# Power.net
KiCad netlist of a schematic drawn in Altium Designer
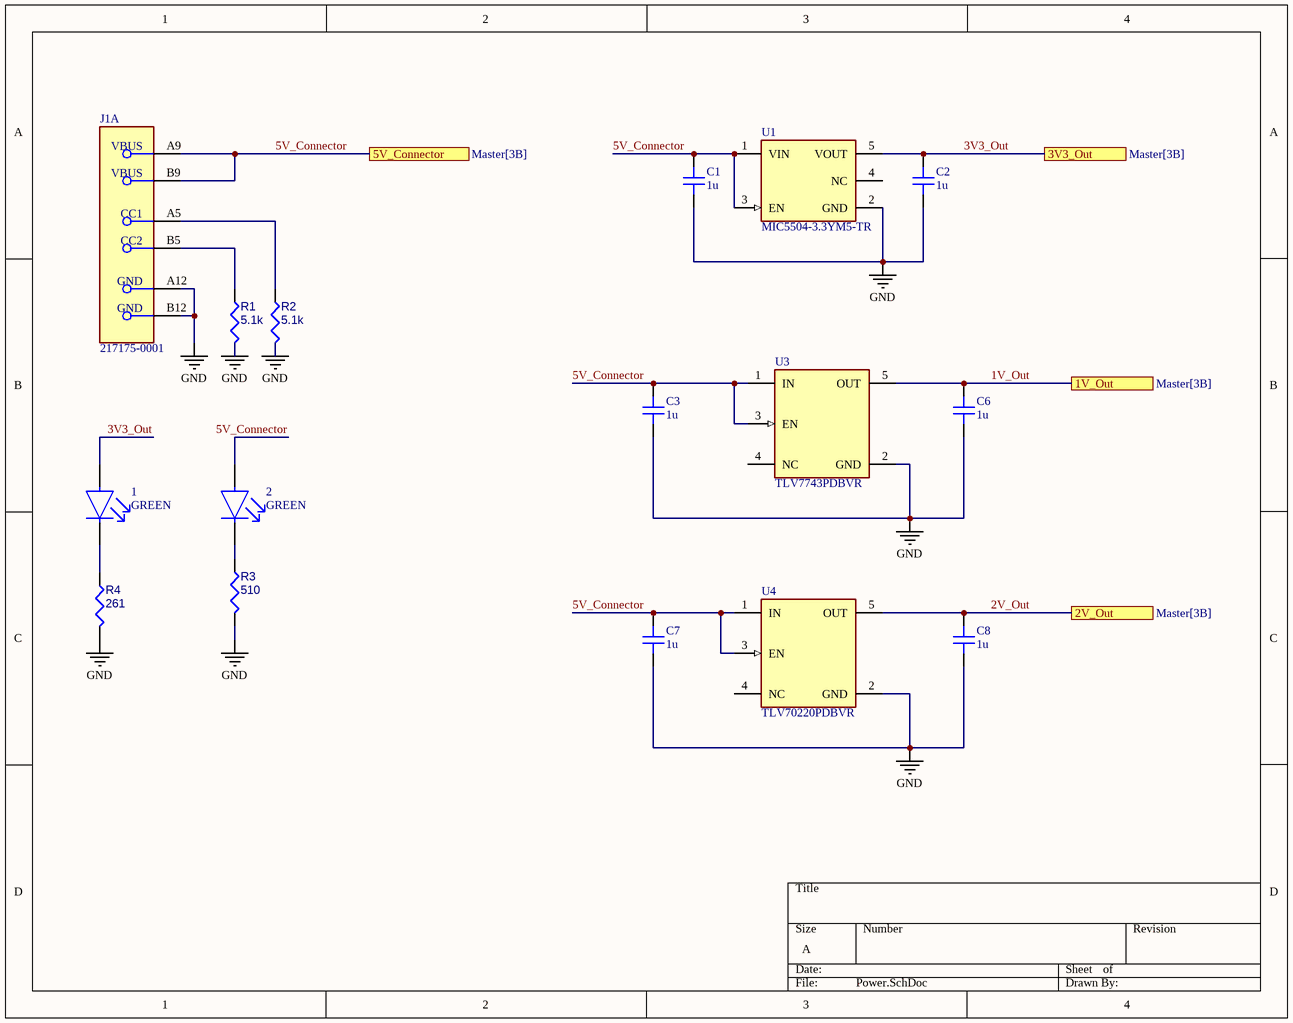
[diagram p0: Power.SchDoc]

(export (version "E")
  (design (tool "Eeschema 10.0.6"))
  (components
    (comp (ref "1")
      (value "GREEN")
      (footprint "FP-ASMT-RF45-AN002-MFG")
      (description "ASMT-RF45-AN002 LED YLW/GREEN DIFFUSED 0603 SMD")
      (fields
        (field (name "MANUFACTURER") "Broadcom")
        (field (name "OCTOPART") "https://octopart.com/asmt-rf45-an002-broadcom-71127304")
      )
      (libsource (lib "Altium Content Vault") (part "8706943c75ba83719d021d2fdc84c58"))
    )
    (comp (ref "2")
      (value "GREEN")
      (footprint "FP-ASMT-RF45-AN002-MFG")
      (description "ASMT-RF45-AN002 LED YLW/GREEN DIFFUSED 0603 SMD")
      (fields
        (field (name "MANUFACTURER") "Broadcom")
        (field (name "OCTOPART") "https://octopart.com/asmt-rf45-an002-broadcom-71127304")
      )
      (libsource (lib "Altium Content Vault") (part "8706943c75ba83719d021d2fdc84c58"))
    )
    (comp (ref "C1")
      (value "1u")
      (footprint "CAP 0603_1608")
      (fields
        (field (name "PART NUMBER") "ZRB18AR6YA475ME05L")
        (field (name "MANUFACTURER") "Murata Electronics")
        (field (name "TOLERANCE") "±20%")
      )
      (libsource (lib "Gopher Motorsports") (part "CAPACITOR"))
    )
    (comp (ref "C2")
      (value "1u")
      (footprint "CAP 0603_1608")
      (fields
        (field (name "PART NUMBER") "ZRB18AR6YA475ME05L")
        (field (name "MANUFACTURER") "Murata Electronics")
        (field (name "TOLERANCE") "±20%")
      )
      (libsource (lib "Gopher Motorsports") (part "CAPACITOR"))
    )
    (comp (ref "C3")
      (value "1u")
      (footprint "CAP 0603_1608")
      (fields
        (field (name "PART NUMBER") "ZRB18AR6YA475ME05L")
        (field (name "MANUFACTURER") "Murata Electronics")
        (field (name "TOLERANCE") "±20%")
      )
      (libsource (lib "Gopher Motorsports") (part "CAPACITOR"))
    )
    (comp (ref "C6")
      (value "1u")
      (footprint "CAP 0603_1608")
      (fields
        (field (name "PART NUMBER") "ZRB18AR6YA475ME05L")
        (field (name "MANUFACTURER") "Murata Electronics")
        (field (name "TOLERANCE") "±20%")
      )
      (libsource (lib "Gopher Motorsports") (part "CAPACITOR"))
    )
    (comp (ref "C7")
      (value "1u")
      (footprint "CAP 0603_1608")
      (fields
        (field (name "PART NUMBER") "ZRB18AR6YA475ME05L")
        (field (name "MANUFACTURER") "Murata Electronics")
        (field (name "TOLERANCE") "±20%")
      )
      (libsource (lib "Gopher Motorsports") (part "CAPACITOR"))
    )
    (comp (ref "C8")
      (value "1u")
      (footprint "CAP 0603_1608")
      (fields
        (field (name "PART NUMBER") "ZRB18AR6YA475ME05L")
        (field (name "MANUFACTURER") "Murata Electronics")
        (field (name "TOLERANCE") "±20%")
      )
      (libsource (lib "Gopher Motorsports") (part "CAPACITOR"))
    )
    (comp (ref "J1")
      (value "217175-0001")
      (footprint "FP-217175-0001-MFG")
      (description "Conn USB 2.0 Type C F 6 POS 1.23mm/1.02mm/1mm Solder RA SMD 6 Terminal 1 Port")
      (libsource (lib "Gopher Motorsports") (part "6a66c69350f09309f94811689c98437"))
    )
    (comp (ref "R1")
      (value "5.1k")
      (footprint "RESC1608X55X25ML10T15")
      (description "Chip Resistor, +/-1%, 0.1 W, -55 to 155 degC, 0603 (1608 Metric)")
      (fields (field (name "POWER") "100mW") (field (name "TOLERANCE") "1%"))
      (libsource (lib "Gopher Motorsports") (part "RES-2"))
    )
    (comp (ref "R2")
      (value "5.1k")
      (footprint "RESC1608X55X25ML10T15")
      (description "Chip Resistor, +/-1%, 0.1 W, -55 to 155 degC, 0603 (1608 Metric)")
      (fields (field (name "POWER") "100mW") (field (name "TOLERANCE") "1%"))
      (libsource (lib "Gopher Motorsports") (part "RES-2"))
    )
    (comp (ref "R3")
      (value "510")
      (footprint "RESC1608X55X25ML10T15")
      (description "Chip Resistor, +/-1%, 0.1 W, -55 to 155 degC, 0603 (1608 Metric)")
      (fields (field (name "POWER") "100mW") (field (name "TOLERANCE") "1%"))
      (libsource (lib "Gopher Motorsports") (part "RES-2"))
    )
    (comp (ref "R4")
      (value "261")
      (footprint "RESC1608X55X25ML10T15")
      (description "Chip Resistor, +/-1%, 0.1 W, -55 to 155 degC, 0603 (1608 Metric)")
      (fields (field (name "POWER") "100mW") (field (name "TOLERANCE") "1%"))
      (libsource (lib "Gopher Motorsports") (part "RES-2"))
    )
    (comp (ref "U1")
      (value "MIC5504-3.3YM5-TR")
      (footprint "FP-SOT23-5LD-PL-1-IPC_B")
      (description "Fixed Positive LDO Regulator, 3.3V, 0.38V Dropout, CMOS, PDSO5")
      (libsource (lib "Gopher Motorsports") (part "96048095611b4a9579e1e315950d302"))
    )
    (comp (ref "U3")
      (value "TLV7743PDBVR")
      (footprint "FP-DBV0005A-IPC_C")
      (description "Fixed Positive LDO Regulator, 2V, CMOS, PDSO5")
      (libsource (lib "Gopher Motorsports") (part "3ee2588bdf7704766daa760b4559fef"))
    )
    (comp (ref "U4")
      (value "TLV70220PDBVR")
      (footprint "FP-DBV0005A-IPC_C")
      (description "Fixed Positive LDO Regulator, 2V, CMOS, PDSO5")
      (libsource (lib "Gopher Motorsports") (part "3ee2588bdf7704766daa760b4559fef"))
    )
  )
  (nets
    (net (code "1") (name "/1V_Out") (class "Default")
      (node (ref "C6") (pin "1") (pinfunction "1_1") (pintype "passive"))
      (node (ref "U3") (pin "5") (pinfunction "OUT_5") (pintype "power_in"))
    )
    (net (code "2") (name "/2V_Out") (class "Default")
      (node (ref "C8") (pin "1") (pinfunction "1_1") (pintype "passive"))
      (node (ref "U4") (pin "5") (pinfunction "OUT_5") (pintype "power_in"))
    )
    (net (code "3") (name "/3V3_Out") (class "Default")
      (node (ref "1") (pin "2") (pinfunction "A_2") (pintype "passive"))
      (node (ref "C2") (pin "1") (pinfunction "1_1") (pintype "passive"))
      (node (ref "U1") (pin "5") (pinfunction "VOUT_5") (pintype "power_in"))
    )
    (net (code "4") (name "/5V_Connector") (class "Default")
      (node (ref "2") (pin "2") (pinfunction "A_2") (pintype "passive"))
      (node (ref "C1") (pin "1") (pinfunction "1_1") (pintype "passive"))
      (node (ref "C3") (pin "1") (pinfunction "1_1") (pintype "passive"))
      (node (ref "C7") (pin "1") (pinfunction "1_1") (pintype "passive"))
      (node (ref "J1") (pin "A9") (pinfunction "VBUS_A9") (pintype "power_in"))
      (node (ref "J1") (pin "B9") (pinfunction "VBUS_B9") (pintype "power_in"))
      (node (ref "U1") (pin "1") (pinfunction "VIN_1") (pintype "power_in"))
      (node (ref "U1") (pin "3") (pinfunction "EN_3") (pintype "input"))
      (node (ref "U3") (pin "1") (pinfunction "IN_1") (pintype "power_in"))
      (node (ref "U3") (pin "3") (pinfunction "EN_3") (pintype "input"))
      (node (ref "U4") (pin "1") (pinfunction "IN_1") (pintype "power_in"))
      (node (ref "U4") (pin "3") (pinfunction "EN_3") (pintype "input"))
    )
    (net (code "5") (name "GND") (class "Default")
      (node (ref "C1") (pin "2") (pinfunction "2_2") (pintype "passive"))
      (node (ref "C2") (pin "2") (pinfunction "2_2") (pintype "passive"))
      (node (ref "C3") (pin "2") (pinfunction "2_2") (pintype "passive"))
      (node (ref "C6") (pin "2") (pinfunction "2_2") (pintype "passive"))
      (node (ref "C7") (pin "2") (pinfunction "2_2") (pintype "passive"))
      (node (ref "C8") (pin "2") (pinfunction "2_2") (pintype "passive"))
      (node (ref "J1") (pin "A12") (pinfunction "GND_A12") (pintype "power_in"))
      (node (ref "J1") (pin "B12") (pinfunction "GND_B12") (pintype "power_in"))
      (node (ref "R1") (pin "2") (pinfunction "2_2") (pintype "passive"))
      (node (ref "R2") (pin "2") (pinfunction "2_2") (pintype "passive"))
      (node (ref "R3") (pin "2") (pinfunction "2_2") (pintype "passive"))
      (node (ref "R4") (pin "2") (pinfunction "2_2") (pintype "passive"))
      (node (ref "U1") (pin "2") (pinfunction "GND_2") (pintype "power_in"))
      (node (ref "U3") (pin "2") (pinfunction "GND_2") (pintype "power_in"))
      (node (ref "U4") (pin "2") (pinfunction "GND_2") (pintype "power_in"))
    )
    (net (code "6") (name "Net-(1-C)") (class "Default")
      (node (ref "1") (pin "1") (pinfunction "C_1") (pintype "passive"))
      (node (ref "R4") (pin "1") (pinfunction "1_1") (pintype "passive"))
    )
    (net (code "7") (name "Net-(2-C)") (class "Default")
      (node (ref "2") (pin "1") (pinfunction "C_1") (pintype "passive"))
      (node (ref "R3") (pin "1") (pinfunction "1_1") (pintype "passive"))
    )
    (net (code "8") (name "Net-(J1A-CC1)") (class "Default")
      (node (ref "J1") (pin "A5") (pinfunction "CC1_A5") (pintype "passive"))
      (node (ref "R2") (pin "1") (pinfunction "1_1") (pintype "passive"))
    )
    (net (code "9") (name "Net-(J1A-CC2)") (class "Default")
      (node (ref "J1") (pin "B5") (pinfunction "CC2_B5") (pintype "passive"))
      (node (ref "R1") (pin "1") (pinfunction "1_1") (pintype "passive"))
    )
    (net (code "10") (name "unconnected-(U1-NC-Pad4)") (class "Default")
      (node (ref "U1") (pin "4") (pinfunction "NC_4") (pintype "passive"))
    )
    (net (code "11") (name "unconnected-(U3-NC-Pad4)") (class "Default")
      (node (ref "U3") (pin "4") (pinfunction "NC_4") (pintype "passive"))
    )
    (net (code "12") (name "unconnected-(U4-NC-Pad4)") (class "Default")
      (node (ref "U4") (pin "4") (pinfunction "NC_4") (pintype "passive"))
    )
  )
)
